# twoinone.net
KiCad netlist of a schematic drawn in Altium Designer
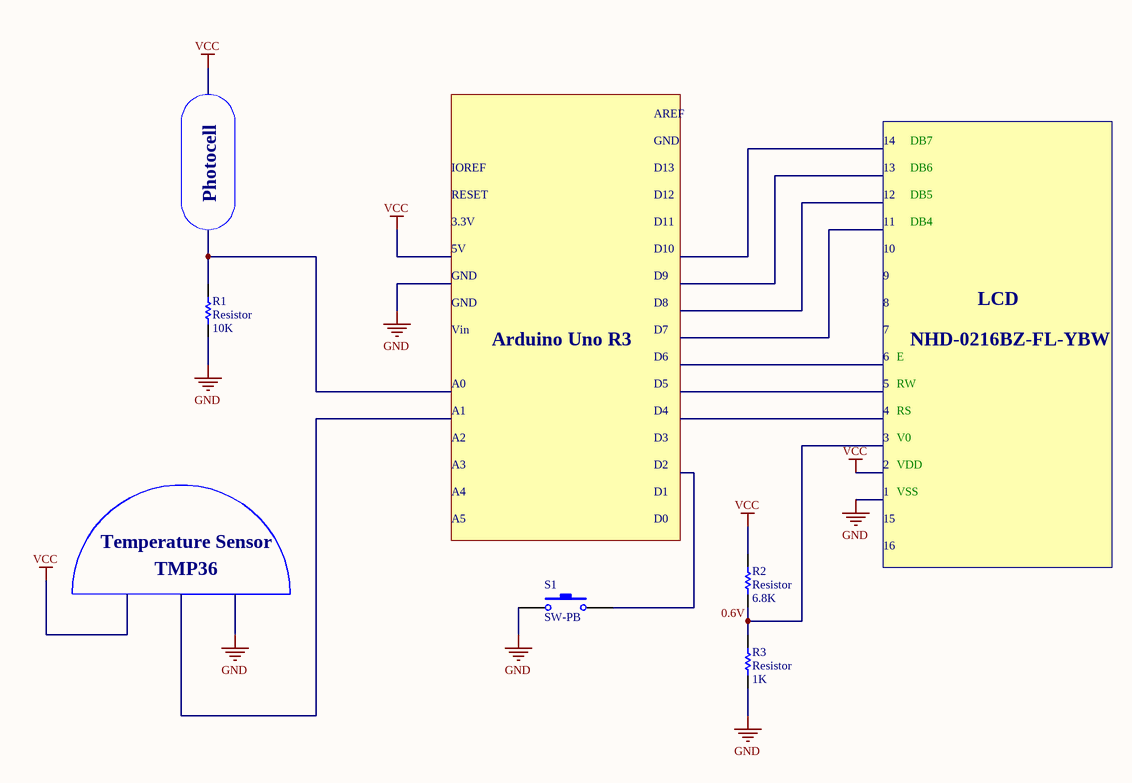
[diagram p0: twoinone.SchDoc]

(export (version "E")
  (design (tool "Eeschema 10.0.6"))
  (components
    (comp (ref "R1")
      (value "Resistor")
      (footprint "AXIAL-0.3")
      (fields (field (name "ALTIUM_VALUE") "10K") (field (name "PUBLISHER") "Altium Limited"))
      (libsource (lib "Miscellaneous Devices") (part "Res1"))
    )
    (comp (ref "R2")
      (value "Resistor")
      (footprint "AXIAL-0.3")
      (fields (field (name "ALTIUM_VALUE") "6.8K") (field (name "PUBLISHER") "Altium Limited"))
      (libsource (lib "Miscellaneous Devices") (part "Res1"))
    )
    (comp (ref "R3")
      (value "Resistor")
      (footprint "AXIAL-0.3")
      (fields (field (name "ALTIUM_VALUE") "1K") (field (name "PUBLISHER") "Altium Limited"))
      (libsource (lib "Miscellaneous Devices") (part "Res1"))
    )
    (comp (ref "S1")
      (value "SW-PB")
      (footprint "SPST-2")
      (description "Switch")
      (fields (field (name "PUBLISHER") "Altium Limited"))
      (libsource (lib "Miscellaneous Devices") (part "SW-PB"))
    )
  )
  (nets
    (net (code "1") (name "GND") (class "Default")
      (node (ref "R1") (pin "1") (pinfunction "1_1") (pintype "passive"))
      (node (ref "R3") (pin "1") (pinfunction "1_1") (pintype "passive"))
      (node (ref "S1") (pin "1") (pinfunction "1_1") (pintype "passive"))
    )
    (net (code "2") (name "Net-(R2-Pad1)") (class "Default")
      (node (ref "R2") (pin "1") (pinfunction "1_1") (pintype "passive"))
      (node (ref "R3") (pin "2") (pinfunction "2_2") (pintype "passive"))
    )
    (net (code "3") (name "VCC") (class "Default")
      (node (ref "R2") (pin "2") (pinfunction "2_2") (pintype "passive"))
    )
    (net (code "4") (name "unconnected-(R1-Pad2)") (class "Default")
      (node (ref "R1") (pin "2") (pinfunction "2_2") (pintype "passive"))
    )
    (net (code "5") (name "unconnected-(S1-Pad2)") (class "Default")
      (node (ref "S1") (pin "2") (pinfunction "2_2") (pintype "passive"))
    )
  )
)
